# I2C_MUX.net
KiCad netlist of a schematic drawn in Altium Designer
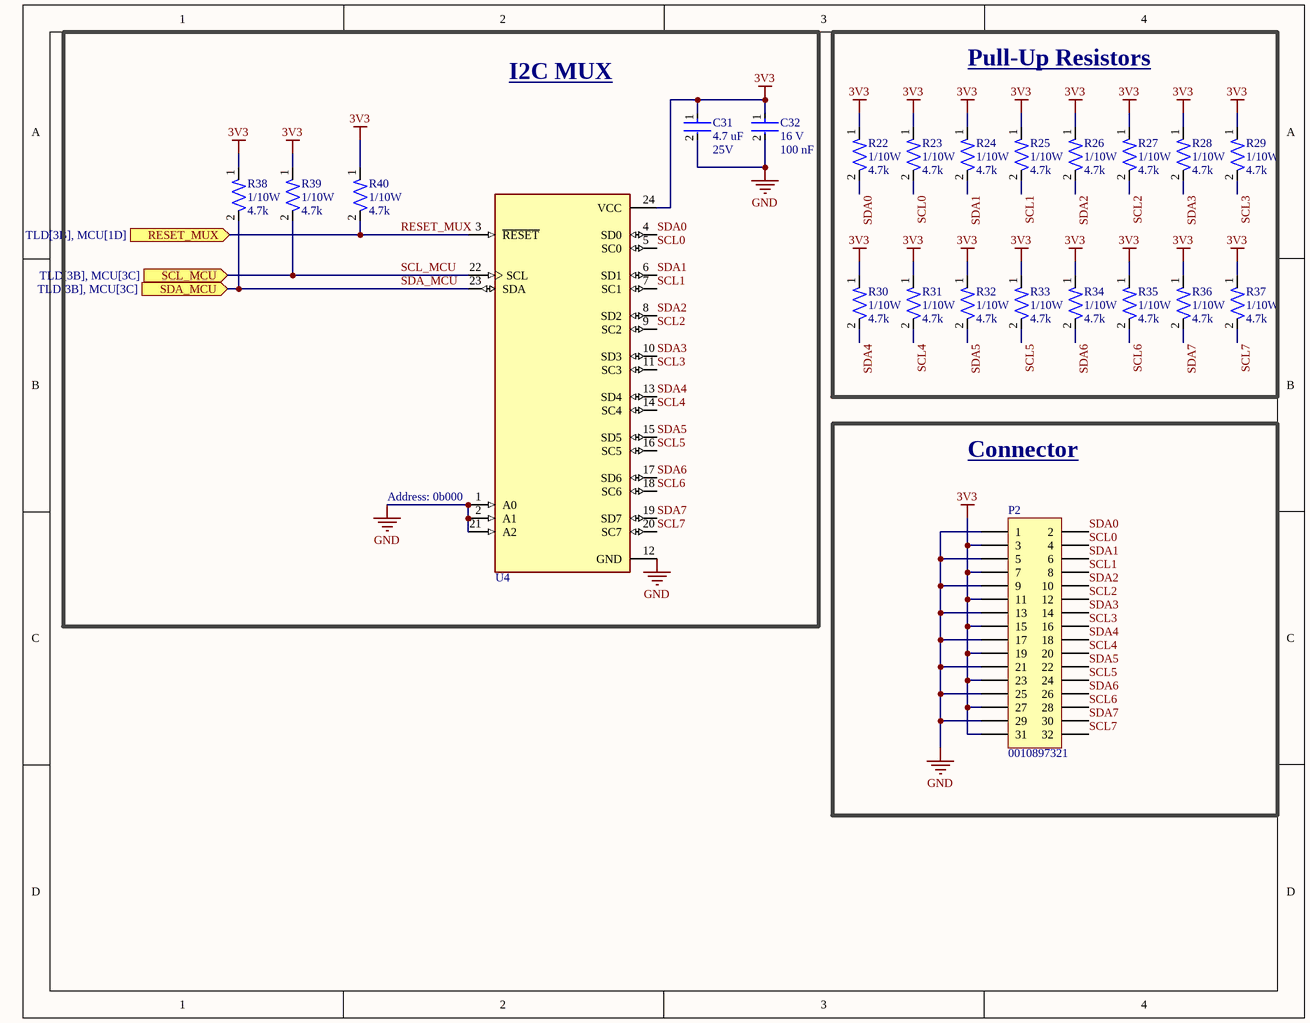
[diagram p0: I2C_MUX.SchDoc]

(export (version "E")
  (design (tool "Eeschema 10.0.6"))
  (components
    (comp (ref "C31")
      (value "CC0603KRX5R8BB475")
      (footprint "CAP-0603")
      (description "CAP CER 4.7UF 25V X5R 0603")
      (fields (field (name "CAPACITANCE") "4.7 uF") (field (name "VOLTAGE") "25V"))
      (libsource (lib "JLC_25") (part "CAP-4.7U-0001"))
    )
    (comp (ref "C32")
      (value "CC0402KRX7R7BB104")
      (footprint "CAP-0402")
      (description "CAP CER 0.1UF 16V X7R 0402")
      (fields (field (name "VOLTAGE RATING") "16 V") (field (name "CAPACITANCE") "100 nF"))
      (libsource (lib "JLC_25") (part "CAP-0.1U-0001"))
    )
    (comp (ref "P2")
      (value "0010897321")
      (footprint "HDR2X16")
      (description "Header, 16-Pin, Dual row")
      (fields (field (name "PUBLISHER") "Altium Limited"))
      (libsource (lib "Miscellaneous Connectors") (part "Header 16X2"))
    )
    (comp (ref "R22")
      (value "RC0603FR-074K7L")
      (footprint "RES-0603")
      (description "RES 4.7K OHM 1% 1/10W 0603")
      (fields
        (field (name "TOLERANCE") "1%")
        (field (name "POWER") "1/10W")
        (field (name "RESISTANCE") "4.7k")
      )
      (libsource (lib "JLC_25") (part "RES-4.7k-0001"))
    )
    (comp (ref "R23")
      (value "RC0603FR-074K7L")
      (footprint "RES-0603")
      (description "RES 4.7K OHM 1% 1/10W 0603")
      (fields
        (field (name "TOLERANCE") "1%")
        (field (name "POWER") "1/10W")
        (field (name "RESISTANCE") "4.7k")
      )
      (libsource (lib "JLC_25") (part "RES-4.7k-0001"))
    )
    (comp (ref "R24")
      (value "RC0603FR-074K7L")
      (footprint "RES-0603")
      (description "RES 4.7K OHM 1% 1/10W 0603")
      (fields
        (field (name "TOLERANCE") "1%")
        (field (name "POWER") "1/10W")
        (field (name "RESISTANCE") "4.7k")
      )
      (libsource (lib "JLC_25") (part "RES-4.7k-0001"))
    )
    (comp (ref "R25")
      (value "RC0603FR-074K7L")
      (footprint "RES-0603")
      (description "RES 4.7K OHM 1% 1/10W 0603")
      (fields
        (field (name "TOLERANCE") "1%")
        (field (name "POWER") "1/10W")
        (field (name "RESISTANCE") "4.7k")
      )
      (libsource (lib "JLC_25") (part "RES-4.7k-0001"))
    )
    (comp (ref "R26")
      (value "RC0603FR-074K7L")
      (footprint "RES-0603")
      (description "RES 4.7K OHM 1% 1/10W 0603")
      (fields
        (field (name "TOLERANCE") "1%")
        (field (name "POWER") "1/10W")
        (field (name "RESISTANCE") "4.7k")
      )
      (libsource (lib "JLC_25") (part "RES-4.7k-0001"))
    )
    (comp (ref "R27")
      (value "RC0603FR-074K7L")
      (footprint "RES-0603")
      (description "RES 4.7K OHM 1% 1/10W 0603")
      (fields
        (field (name "TOLERANCE") "1%")
        (field (name "POWER") "1/10W")
        (field (name "RESISTANCE") "4.7k")
      )
      (libsource (lib "JLC_25") (part "RES-4.7k-0001"))
    )
    (comp (ref "R28")
      (value "RC0603FR-074K7L")
      (footprint "RES-0603")
      (description "RES 4.7K OHM 1% 1/10W 0603")
      (fields
        (field (name "TOLERANCE") "1%")
        (field (name "POWER") "1/10W")
        (field (name "RESISTANCE") "4.7k")
      )
      (libsource (lib "JLC_25") (part "RES-4.7k-0001"))
    )
    (comp (ref "R29")
      (value "RC0603FR-074K7L")
      (footprint "RES-0603")
      (description "RES 4.7K OHM 1% 1/10W 0603")
      (fields
        (field (name "TOLERANCE") "1%")
        (field (name "POWER") "1/10W")
        (field (name "RESISTANCE") "4.7k")
      )
      (libsource (lib "JLC_25") (part "RES-4.7k-0001"))
    )
    (comp (ref "R30")
      (value "RC0603FR-074K7L")
      (footprint "RES-0603")
      (description "RES 4.7K OHM 1% 1/10W 0603")
      (fields
        (field (name "TOLERANCE") "1%")
        (field (name "POWER") "1/10W")
        (field (name "RESISTANCE") "4.7k")
      )
      (libsource (lib "JLC_25") (part "RES-4.7k-0001"))
    )
    (comp (ref "R31")
      (value "RC0603FR-074K7L")
      (footprint "RES-0603")
      (description "RES 4.7K OHM 1% 1/10W 0603")
      (fields
        (field (name "TOLERANCE") "1%")
        (field (name "POWER") "1/10W")
        (field (name "RESISTANCE") "4.7k")
      )
      (libsource (lib "JLC_25") (part "RES-4.7k-0001"))
    )
    (comp (ref "R32")
      (value "RC0603FR-074K7L")
      (footprint "RES-0603")
      (description "RES 4.7K OHM 1% 1/10W 0603")
      (fields
        (field (name "TOLERANCE") "1%")
        (field (name "POWER") "1/10W")
        (field (name "RESISTANCE") "4.7k")
      )
      (libsource (lib "JLC_25") (part "RES-4.7k-0001"))
    )
    (comp (ref "R33")
      (value "RC0603FR-074K7L")
      (footprint "RES-0603")
      (description "RES 4.7K OHM 1% 1/10W 0603")
      (fields
        (field (name "TOLERANCE") "1%")
        (field (name "POWER") "1/10W")
        (field (name "RESISTANCE") "4.7k")
      )
      (libsource (lib "JLC_25") (part "RES-4.7k-0001"))
    )
    (comp (ref "R34")
      (value "RC0603FR-074K7L")
      (footprint "RES-0603")
      (description "RES 4.7K OHM 1% 1/10W 0603")
      (fields
        (field (name "TOLERANCE") "1%")
        (field (name "POWER") "1/10W")
        (field (name "RESISTANCE") "4.7k")
      )
      (libsource (lib "JLC_25") (part "RES-4.7k-0001"))
    )
    (comp (ref "R35")
      (value "RC0603FR-074K7L")
      (footprint "RES-0603")
      (description "RES 4.7K OHM 1% 1/10W 0603")
      (fields
        (field (name "TOLERANCE") "1%")
        (field (name "POWER") "1/10W")
        (field (name "RESISTANCE") "4.7k")
      )
      (libsource (lib "JLC_25") (part "RES-4.7k-0001"))
    )
    (comp (ref "R36")
      (value "RC0603FR-074K7L")
      (footprint "RES-0603")
      (description "RES 4.7K OHM 1% 1/10W 0603")
      (fields
        (field (name "TOLERANCE") "1%")
        (field (name "POWER") "1/10W")
        (field (name "RESISTANCE") "4.7k")
      )
      (libsource (lib "JLC_25") (part "RES-4.7k-0001"))
    )
    (comp (ref "R37")
      (value "RC0603FR-074K7L")
      (footprint "RES-0603")
      (description "RES 4.7K OHM 1% 1/10W 0603")
      (fields
        (field (name "TOLERANCE") "1%")
        (field (name "POWER") "1/10W")
        (field (name "RESISTANCE") "4.7k")
      )
      (libsource (lib "JLC_25") (part "RES-4.7k-0001"))
    )
    (comp (ref "R38")
      (value "RC0603FR-074K7L")
      (footprint "RES-0603")
      (description "RES 4.7K OHM 1% 1/10W 0603")
      (fields
        (field (name "TOLERANCE") "1%")
        (field (name "POWER") "1/10W")
        (field (name "RESISTANCE") "4.7k")
      )
      (libsource (lib "JLC_25") (part "RES-4.7k-0001"))
    )
    (comp (ref "R39")
      (value "RC0603FR-074K7L")
      (footprint "RES-0603")
      (description "RES 4.7K OHM 1% 1/10W 0603")
      (fields
        (field (name "TOLERANCE") "1%")
        (field (name "POWER") "1/10W")
        (field (name "RESISTANCE") "4.7k")
      )
      (libsource (lib "JLC_25") (part "RES-4.7k-0001"))
    )
    (comp (ref "R40")
      (value "RC0603FR-074K7L")
      (footprint "RES-0603")
      (description "RES 4.7K OHM 1% 1/10W 0603")
      (fields
        (field (name "TOLERANCE") "1%")
        (field (name "POWER") "1/10W")
        (field (name "RESISTANCE") "4.7k")
      )
      (libsource (lib "JLC_25") (part "RES-4.7k-0001"))
    )
    (comp (ref "U4")
      (value "TCA9548APWR")
      (footprint "SOP65P640X120-24N")
      (description "8-channel 1.65- to 5.5-V I2C/SMBus switch with reset & voltage translation")
      (fields (field (name "MF") "Texas Instruments"))
      (libsource (lib "JLC_25") (part "IC-MUX-0002"))
    )
  )
  (nets
    (net (code "1") (name "/RESET_MUX") (class "Default")
      (node (ref "R40") (pin "2") (pinfunction "2_2") (pintype "passive"))
      (node (ref "U4") (pin "3") (pinfunction "~{RESET}_3") (pintype "input"))
    )
    (net (code "2") (name "/SCL0") (class "Default")
      (node (ref "P2") (pin "4") (pinfunction "4_4") (pintype "passive"))
      (node (ref "R23") (pin "2") (pinfunction "2_2") (pintype "passive"))
      (node (ref "U4") (pin "5") (pinfunction "SC0_5") (pintype "bidirectional"))
    )
    (net (code "3") (name "/SCL1") (class "Default")
      (node (ref "P2") (pin "8") (pinfunction "8_8") (pintype "passive"))
      (node (ref "R25") (pin "2") (pinfunction "2_2") (pintype "passive"))
      (node (ref "U4") (pin "7") (pinfunction "SC1_7") (pintype "bidirectional"))
    )
    (net (code "4") (name "/SCL2") (class "Default")
      (node (ref "P2") (pin "12") (pinfunction "12_12") (pintype "passive"))
      (node (ref "R27") (pin "2") (pinfunction "2_2") (pintype "passive"))
      (node (ref "U4") (pin "9") (pinfunction "SC2_9") (pintype "bidirectional"))
    )
    (net (code "5") (name "/SCL3") (class "Default")
      (node (ref "P2") (pin "16") (pinfunction "16_16") (pintype "passive"))
      (node (ref "R29") (pin "2") (pinfunction "2_2") (pintype "passive"))
      (node (ref "U4") (pin "11") (pinfunction "SC3_11") (pintype "bidirectional"))
    )
    (net (code "6") (name "/SCL4") (class "Default")
      (node (ref "P2") (pin "20") (pinfunction "20_20") (pintype "passive"))
      (node (ref "R31") (pin "2") (pinfunction "2_2") (pintype "passive"))
      (node (ref "U4") (pin "14") (pinfunction "SC4_14") (pintype "bidirectional"))
    )
    (net (code "7") (name "/SCL5") (class "Default")
      (node (ref "P2") (pin "24") (pinfunction "24_24") (pintype "passive"))
      (node (ref "R33") (pin "2") (pinfunction "2_2") (pintype "passive"))
      (node (ref "U4") (pin "16") (pinfunction "SC5_16") (pintype "bidirectional"))
    )
    (net (code "8") (name "/SCL6") (class "Default")
      (node (ref "P2") (pin "28") (pinfunction "28_28") (pintype "passive"))
      (node (ref "R35") (pin "2") (pinfunction "2_2") (pintype "passive"))
      (node (ref "U4") (pin "18") (pinfunction "SC6_18") (pintype "bidirectional"))
    )
    (net (code "9") (name "/SCL7") (class "Default")
      (node (ref "P2") (pin "32") (pinfunction "32_32") (pintype "passive"))
      (node (ref "R37") (pin "2") (pinfunction "2_2") (pintype "passive"))
      (node (ref "U4") (pin "20") (pinfunction "SC7_20") (pintype "bidirectional"))
    )
    (net (code "10") (name "/SCL_MCU") (class "Default")
      (node (ref "R39") (pin "2") (pinfunction "2_2") (pintype "passive"))
      (node (ref "U4") (pin "22") (pinfunction "SCL_22") (pintype "input"))
    )
    (net (code "11") (name "/SDA0") (class "Default")
      (node (ref "P2") (pin "2") (pinfunction "2_2") (pintype "passive"))
      (node (ref "R22") (pin "2") (pinfunction "2_2") (pintype "passive"))
      (node (ref "U4") (pin "4") (pinfunction "SD0_4") (pintype "bidirectional"))
    )
    (net (code "12") (name "/SDA1") (class "Default")
      (node (ref "P2") (pin "6") (pinfunction "6_6") (pintype "passive"))
      (node (ref "R24") (pin "2") (pinfunction "2_2") (pintype "passive"))
      (node (ref "U4") (pin "6") (pinfunction "SD1_6") (pintype "bidirectional"))
    )
    (net (code "13") (name "/SDA2") (class "Default")
      (node (ref "P2") (pin "10") (pinfunction "10_10") (pintype "passive"))
      (node (ref "R26") (pin "2") (pinfunction "2_2") (pintype "passive"))
      (node (ref "U4") (pin "8") (pinfunction "SD2_8") (pintype "bidirectional"))
    )
    (net (code "14") (name "/SDA3") (class "Default")
      (node (ref "P2") (pin "14") (pinfunction "14_14") (pintype "passive"))
      (node (ref "R28") (pin "2") (pinfunction "2_2") (pintype "passive"))
      (node (ref "U4") (pin "10") (pinfunction "SD3_10") (pintype "bidirectional"))
    )
    (net (code "15") (name "/SDA4") (class "Default")
      (node (ref "P2") (pin "18") (pinfunction "18_18") (pintype "passive"))
      (node (ref "R30") (pin "2") (pinfunction "2_2") (pintype "passive"))
      (node (ref "U4") (pin "13") (pinfunction "SD4_13") (pintype "bidirectional"))
    )
    (net (code "16") (name "/SDA5") (class "Default")
      (node (ref "P2") (pin "22") (pinfunction "22_22") (pintype "passive"))
      (node (ref "R32") (pin "2") (pinfunction "2_2") (pintype "passive"))
      (node (ref "U4") (pin "15") (pinfunction "SD5_15") (pintype "bidirectional"))
    )
    (net (code "17") (name "/SDA6") (class "Default")
      (node (ref "P2") (pin "26") (pinfunction "26_26") (pintype "passive"))
      (node (ref "R34") (pin "2") (pinfunction "2_2") (pintype "passive"))
      (node (ref "U4") (pin "17") (pinfunction "SD6_17") (pintype "bidirectional"))
    )
    (net (code "18") (name "/SDA7") (class "Default")
      (node (ref "P2") (pin "30") (pinfunction "30_30") (pintype "passive"))
      (node (ref "R36") (pin "2") (pinfunction "2_2") (pintype "passive"))
      (node (ref "U4") (pin "19") (pinfunction "SD7_19") (pintype "bidirectional"))
    )
    (net (code "19") (name "/SDA_MCU") (class "Default")
      (node (ref "R38") (pin "2") (pinfunction "2_2") (pintype "passive"))
      (node (ref "U4") (pin "23") (pinfunction "SDA_23") (pintype "bidirectional"))
    )
    (net (code "20") (name "3V3") (class "Default")
      (node (ref "C31") (pin "1") (pinfunction "1_1") (pintype "passive"))
      (node (ref "C32") (pin "1") (pinfunction "1_1") (pintype "passive"))
      (node (ref "P2") (pin "11") (pinfunction "11_11") (pintype "passive"))
      (node (ref "P2") (pin "15") (pinfunction "15_15") (pintype "passive"))
      (node (ref "P2") (pin "19") (pinfunction "19_19") (pintype "passive"))
      (node (ref "P2") (pin "23") (pinfunction "23_23") (pintype "passive"))
      (node (ref "P2") (pin "27") (pinfunction "27_27") (pintype "passive"))
      (node (ref "P2") (pin "3") (pinfunction "3_3") (pintype "passive"))
      (node (ref "P2") (pin "31") (pinfunction "31_31") (pintype "passive"))
      (node (ref "P2") (pin "7") (pinfunction "7_7") (pintype "passive"))
      (node (ref "R22") (pin "1") (pinfunction "1_1") (pintype "passive"))
      (node (ref "R23") (pin "1") (pinfunction "1_1") (pintype "passive"))
      (node (ref "R24") (pin "1") (pinfunction "1_1") (pintype "passive"))
      (node (ref "R25") (pin "1") (pinfunction "1_1") (pintype "passive"))
      (node (ref "R26") (pin "1") (pinfunction "1_1") (pintype "passive"))
      (node (ref "R27") (pin "1") (pinfunction "1_1") (pintype "passive"))
      (node (ref "R28") (pin "1") (pinfunction "1_1") (pintype "passive"))
      (node (ref "R29") (pin "1") (pinfunction "1_1") (pintype "passive"))
      (node (ref "R30") (pin "1") (pinfunction "1_1") (pintype "passive"))
      (node (ref "R31") (pin "1") (pinfunction "1_1") (pintype "passive"))
      (node (ref "R32") (pin "1") (pinfunction "1_1") (pintype "passive"))
      (node (ref "R33") (pin "1") (pinfunction "1_1") (pintype "passive"))
      (node (ref "R34") (pin "1") (pinfunction "1_1") (pintype "passive"))
      (node (ref "R35") (pin "1") (pinfunction "1_1") (pintype "passive"))
      (node (ref "R36") (pin "1") (pinfunction "1_1") (pintype "passive"))
      (node (ref "R37") (pin "1") (pinfunction "1_1") (pintype "passive"))
      (node (ref "R38") (pin "1") (pinfunction "1_1") (pintype "passive"))
      (node (ref "R39") (pin "1") (pinfunction "1_1") (pintype "passive"))
      (node (ref "R40") (pin "1") (pinfunction "1_1") (pintype "passive"))
      (node (ref "U4") (pin "24") (pinfunction "VCC_24") (pintype "power_in"))
    )
    (net (code "21") (name "GND") (class "Default")
      (node (ref "C31") (pin "2") (pinfunction "2_2") (pintype "passive"))
      (node (ref "C32") (pin "2") (pinfunction "2_2") (pintype "passive"))
      (node (ref "P2") (pin "1") (pinfunction "1_1") (pintype "passive"))
      (node (ref "P2") (pin "13") (pinfunction "13_13") (pintype "passive"))
      (node (ref "P2") (pin "17") (pinfunction "17_17") (pintype "passive"))
      (node (ref "P2") (pin "21") (pinfunction "21_21") (pintype "passive"))
      (node (ref "P2") (pin "25") (pinfunction "25_25") (pintype "passive"))
      (node (ref "P2") (pin "29") (pinfunction "29_29") (pintype "passive"))
      (node (ref "P2") (pin "5") (pinfunction "5_5") (pintype "passive"))
      (node (ref "P2") (pin "9") (pinfunction "9_9") (pintype "passive"))
      (node (ref "U4") (pin "1") (pinfunction "A0_1") (pintype "input"))
      (node (ref "U4") (pin "12") (pinfunction "GND_12") (pintype "power_in"))
      (node (ref "U4") (pin "2") (pinfunction "A1_2") (pintype "input"))
      (node (ref "U4") (pin "21") (pinfunction "A2_21") (pintype "input"))
    )
  )
)
